# Output.net
KiCad netlist of a schematic drawn in Altium Designer
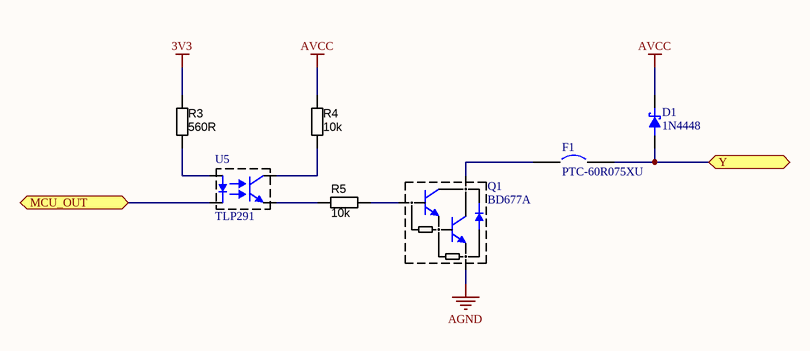
[diagram p0: Output.SchDoc]

(export (version "E")
  (design (tool "Eeschema 10.0.6"))
  (components
    (comp (ref "D1")
      (value "1N4448")
      (footprint "PcbLib:SOD323")
      (description "SURFACE MOUNT FAST SWITCHING DIODE")
      (libsource (lib "Diode") (part "1N4448"))
    )
    (comp (ref "F1")
      (value "PTC-60R075XU")
      (footprint "SPST-60R075XU")
      (description "PTC .75A 60V RESETTABLE KINK")
      (fields (field (name "PUBLISHER") "Altium Limited"))
      (libsource (lib "Connectors") (part "PTC-60R075XU"))
    )
    (comp (ref "Q1")
      (value "BD677A")
      (footprint "Transistors:TO-126")
      (description "Bipolar (BJT) Transistor NPN - Darlington 60V 4A 40W Through Hole SOT-32-3")
      (libsource (lib "Transistors") (part "BD677A"))
    )
    (comp (ref "R3")
      (value "560R")
      (footprint "IPC-7352 Chip_Resistor_N:RESC1608N")
      (description "Resistor SMD chip")
      (fields (field (name "TOLERANCE") "?%"))
      (libsource (lib "LCR Devices") (part "Resistor SMD chip"))
    )
    (comp (ref "R4")
      (value "10k")
      (footprint "IPC-7352 Chip_Resistor_N:RESC1608N")
      (description "Resistor SMD chip")
      (fields (field (name "TOLERANCE") "?%"))
      (libsource (lib "LCR Devices") (part "Resistor SMD chip"))
    )
    (comp (ref "R5")
      (value "10k")
      (footprint "IPC-7352 Chip_Resistor_N:RESC1608N")
      (description "Resistor SMD chip")
      (fields (field (name "TOLERANCE") "?%"))
      (libsource (lib "") (part "Resistor SMD chip_1"))
    )
    (comp (ref "U5")
      (value "TLP291")
      (footprint "Transistors:SO4_N")
      (description "Optoisolator Transistor Output 3750Vrms 1 Channel 4-SO")
      (libsource (lib "Transistors") (part "TLP291"))
    )
  )
  (nets
    (net (code "1") (name "/MCU_OUT") (class "Default")
      (node (ref "U5") (pin "2") (pinfunction "CATHODE_2") (pintype "passive"))
    )
    (net (code "2") (name "/Y") (class "Default")
      (node (ref "D1") (pin "2") (pinfunction "anode_2") (pintype "passive"))
      (node (ref "F1") (pin "2") (pinfunction "2_2") (pintype "passive"))
    )
    (net (code "3") (name "3V3") (class "Default")
      (node (ref "R3") (pin "1") (pinfunction "1_1") (pintype "passive"))
    )
    (net (code "4") (name "AGND") (class "Default")
      (node (ref "Q1") (pin "3") (pinfunction "E_3") (pintype "passive"))
    )
    (net (code "5") (name "AVCC") (class "Default")
      (node (ref "D1") (pin "1") (pinfunction "cathode_1") (pintype "passive"))
      (node (ref "R4") (pin "1") (pinfunction "1_1") (pintype "passive"))
    )
    (net (code "6") (name "Net-(Q1-B)") (class "Default")
      (node (ref "Q1") (pin "1") (pinfunction "B_1") (pintype "passive"))
      (node (ref "R5") (pin "2") (pinfunction "2_2") (pintype "passive"))
    )
    (net (code "7") (name "Net-(Q1-C)") (class "Default")
      (node (ref "F1") (pin "1") (pinfunction "1_1") (pintype "passive"))
      (node (ref "Q1") (pin "2") (pinfunction "C_2") (pintype "passive"))
    )
    (net (code "8") (name "Net-(U5-ANODE)") (class "Default")
      (node (ref "R3") (pin "2") (pinfunction "2_2") (pintype "passive"))
      (node (ref "U5") (pin "1") (pinfunction "ANODE_1") (pintype "passive"))
    )
    (net (code "9") (name "Net-(U5-COLLECTOR)") (class "Default")
      (node (ref "R4") (pin "2") (pinfunction "2_2") (pintype "passive"))
      (node (ref "U5") (pin "4") (pinfunction "COLLECTOR_4") (pintype "passive"))
    )
    (net (code "10") (name "Net-(U5-EMITTER)") (class "Default")
      (node (ref "R5") (pin "1") (pinfunction "1_1") (pintype "passive"))
      (node (ref "U5") (pin "3") (pinfunction "EMITTER_3") (pintype "passive"))
    )
  )
)
